# ECU_1A.net
KiCad netlist of a schematic drawn in EAGLE
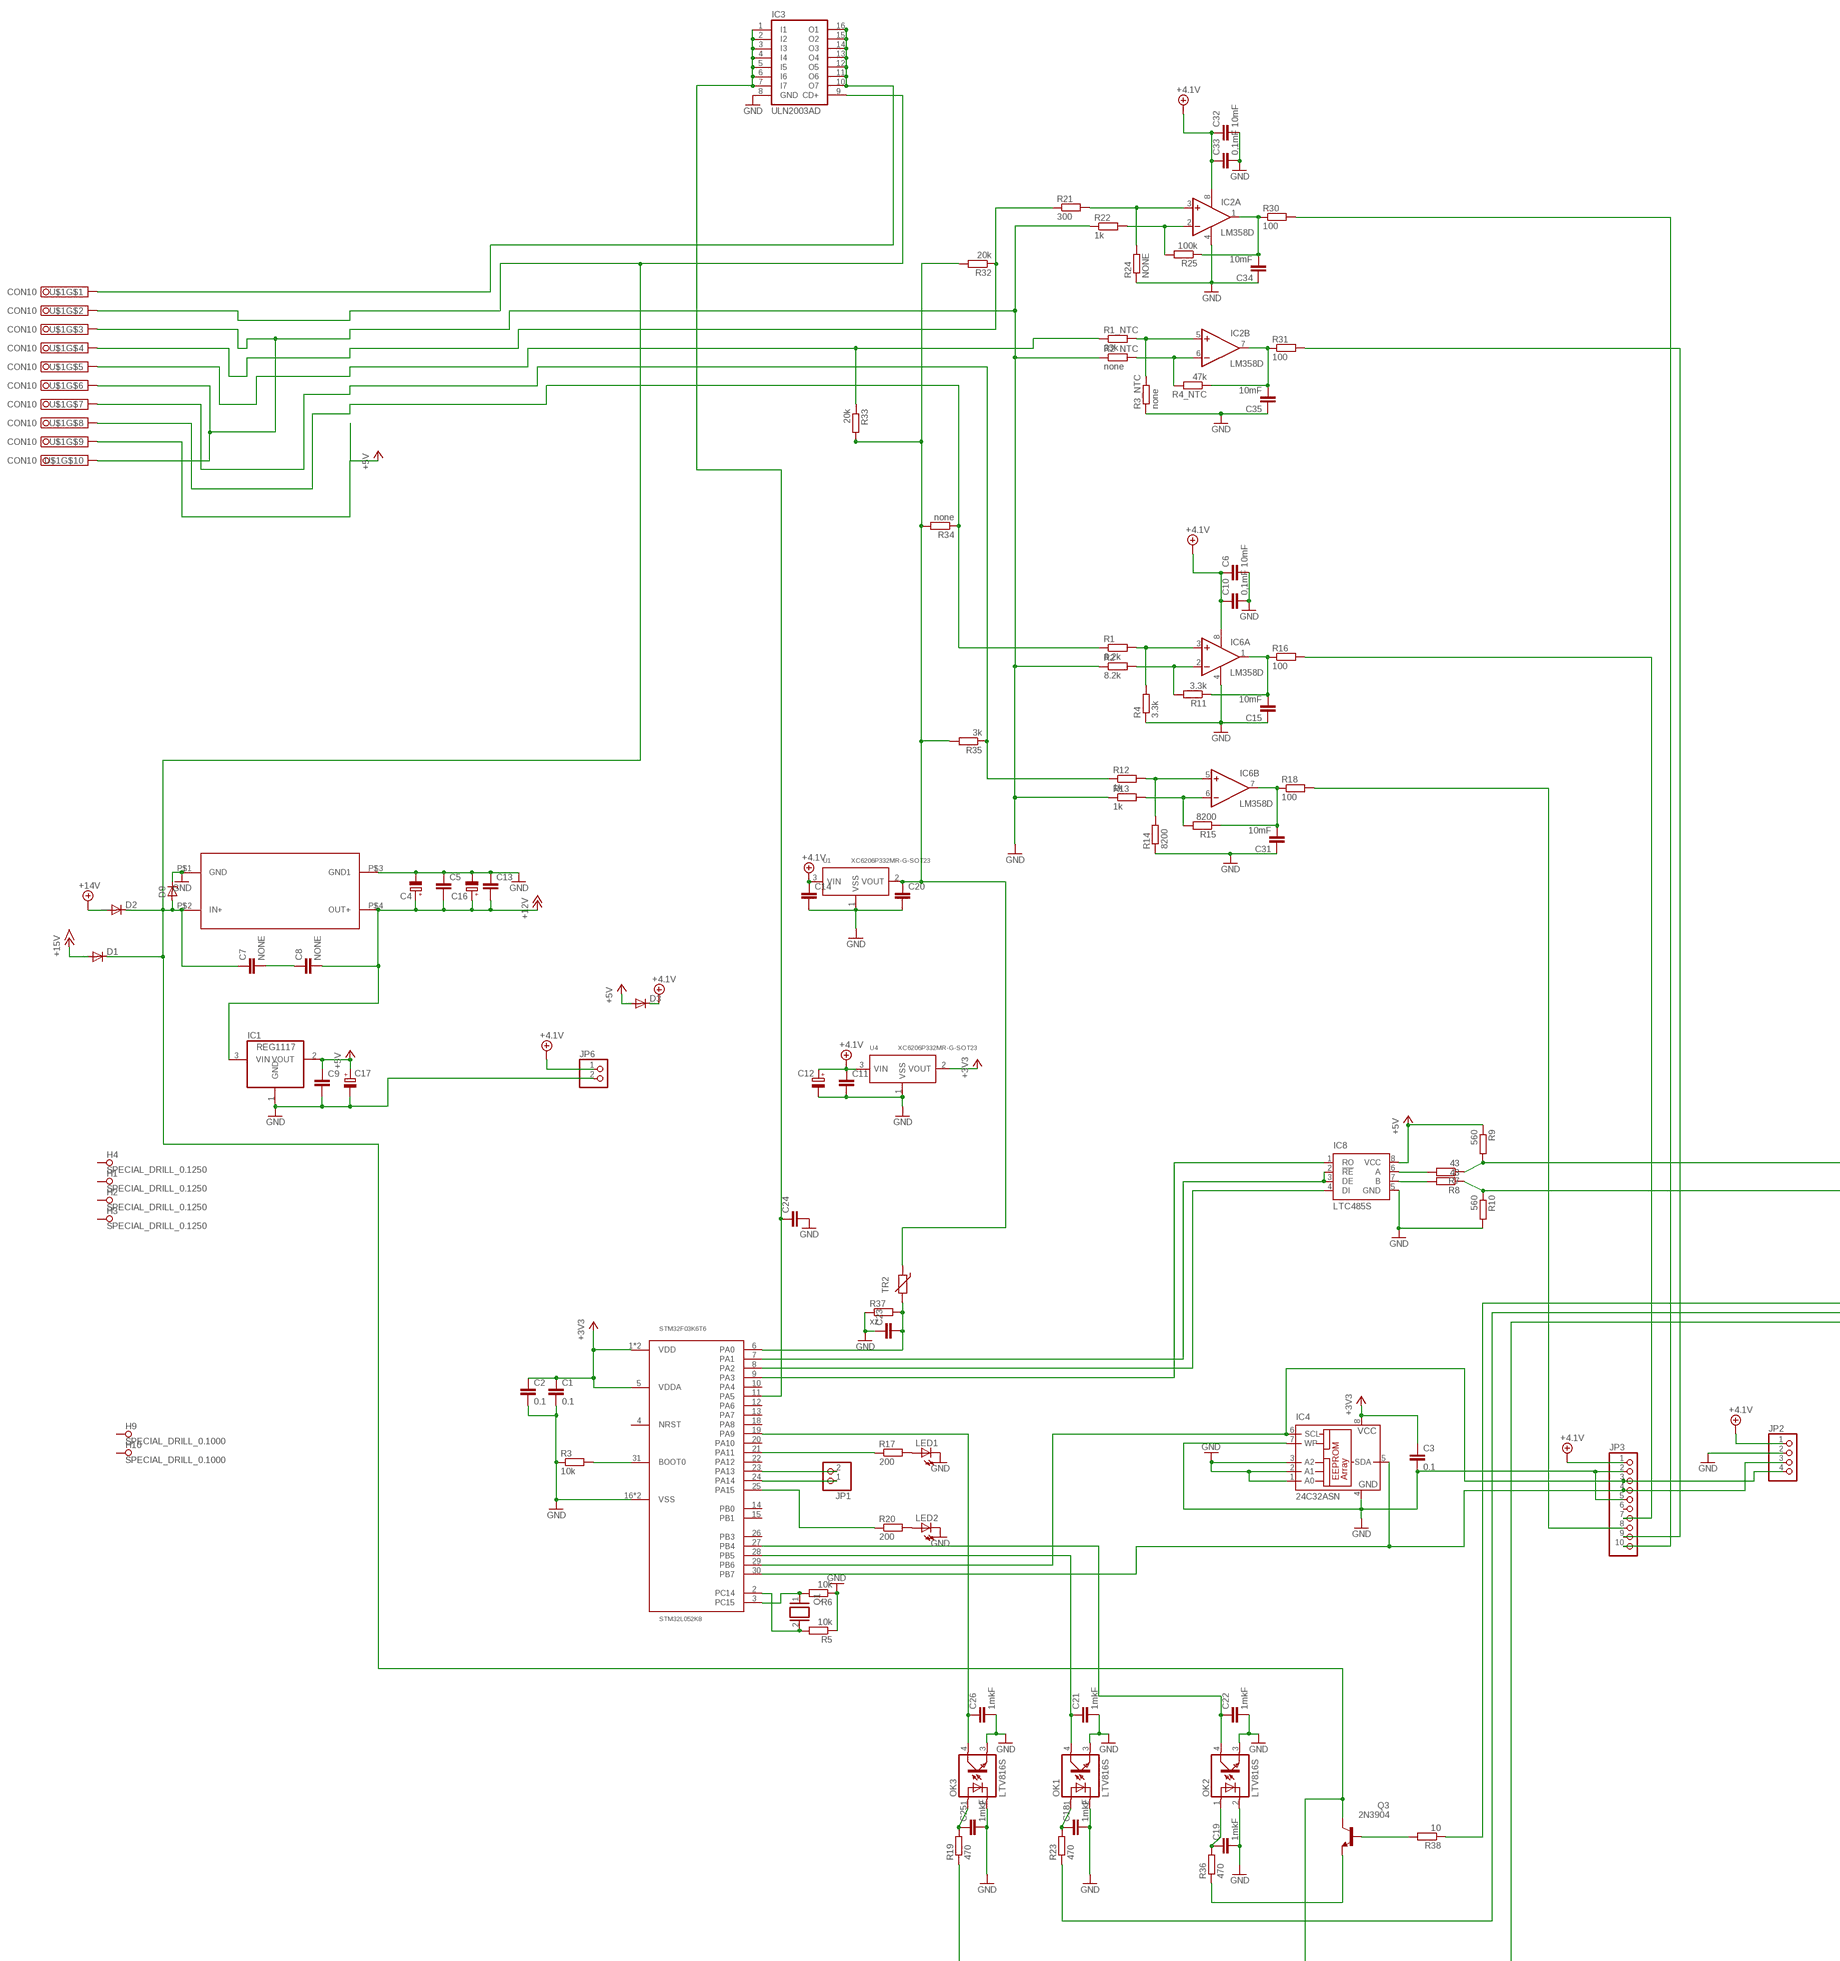
[diagram p0: schematic, sheet 1, part 1 of 3]
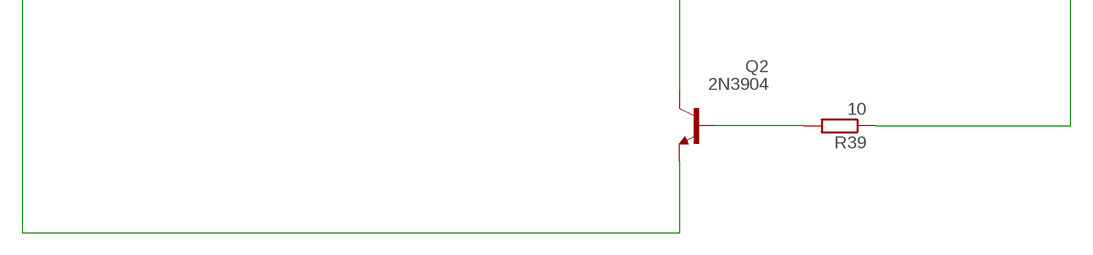
[diagram p1: schematic, sheet 1, part 2 of 3]
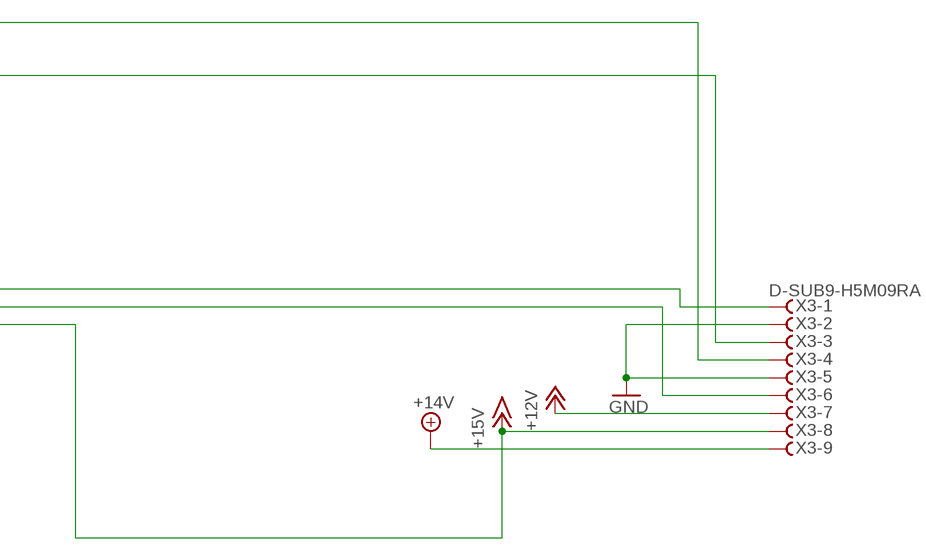
[diagram p2: schematic, sheet 1, part 3 of 3]

(export (version "E")
  (design (tool "Eeschema 10.0.6"))
  (components
    (comp (ref "C1")
      (value "0.1")
      (footprint "eagle-import:C0805")
      (libsource (lib "eagle-import") (part "rcl_C-EUC0805"))
    )
    (comp (ref "C2")
      (value "0.1")
      (footprint "eagle-import:C0805")
      (libsource (lib "eagle-import") (part "rcl_C-EUC0805"))
    )
    (comp (ref "C3")
      (value "0.1")
      (footprint "eagle-import:C0805")
      (libsource (lib "eagle-import") (part "rcl_C-EUC0805"))
    )
    (comp (ref "C4")
      (value "CPOL-EUE2.5-6")
      (footprint "eagle-import:E2,5-6")
      (libsource (lib "eagle-import") (part "CPOL-EUE2.5-6"))
    )
    (comp (ref "C5")
      (value "C-EUC0805")
      (footprint "eagle-import:C0805")
      (libsource (lib "eagle-import") (part "C-EUC0805"))
    )
    (comp (ref "C6")
      (value "10mF")
      (footprint "eagle-import:C0805")
      (libsource (lib "eagle-import") (part "C-EUC0805"))
    )
    (comp (ref "C7")
      (value "NONE")
      (footprint "eagle-import:C0805")
      (libsource (lib "eagle-import") (part "C-EUC0805"))
    )
    (comp (ref "C8")
      (value "NONE")
      (footprint "eagle-import:C0805")
      (libsource (lib "eagle-import") (part "C-EUC0805"))
    )
    (comp (ref "C9")
      (value "C-EUC0805")
      (footprint "eagle-import:C0805")
      (libsource (lib "eagle-import") (part "C-EUC0805"))
    )
    (comp (ref "C10")
      (value "0,1mF")
      (footprint "eagle-import:C0805")
      (libsource (lib "eagle-import") (part "C-EUC0805"))
    )
    (comp (ref "C11")
      (value "C-EUC0805")
      (footprint "eagle-import:C0805")
      (libsource (lib "eagle-import") (part "C-EUC0805"))
    )
    (comp (ref "C12")
      (value "CPOL-EUE2.5-6")
      (footprint "eagle-import:E2,5-6")
      (libsource (lib "eagle-import") (part "CPOL-EUE2.5-6"))
    )
    (comp (ref "C13")
      (value "C-EUC0805")
      (footprint "eagle-import:C0805")
      (libsource (lib "eagle-import") (part "C-EUC0805"))
    )
    (comp (ref "C14")
      (value "C-EUC0805")
      (footprint "eagle-import:C0805")
      (libsource (lib "eagle-import") (part "C-EUC0805"))
    )
    (comp (ref "C15")
      (value "10mF")
      (footprint "eagle-import:C0805")
      (libsource (lib "eagle-import") (part "C-EUC0805"))
    )
    (comp (ref "C16")
      (value "CPOL-EUE5-10.5")
      (footprint "eagle-import:E5-10,5")
      (libsource (lib "eagle-import") (part "rcl_CPOL-EUE5-10.5"))
    )
    (comp (ref "C17")
      (value "CPOL-EUE2,5-6E")
      (footprint "eagle-import:E2,5-6E")
      (libsource (lib "eagle-import") (part "rcl_CPOL-EUE2,5-6E"))
    )
    (comp (ref "C18")
      (value "1mkF")
      (footprint "eagle-import:C0805")
      (libsource (lib "eagle-import") (part "rcl_C-EUC0805"))
    )
    (comp (ref "C19")
      (value "1mkF")
      (footprint "eagle-import:C0805")
      (libsource (lib "eagle-import") (part "rcl_C-EUC0805"))
    )
    (comp (ref "C20")
      (value "C-EUC0805")
      (footprint "eagle-import:C0805")
      (libsource (lib "eagle-import") (part "C-EUC0805"))
    )
    (comp (ref "C21")
      (value "1mkF")
      (footprint "eagle-import:C0805")
      (libsource (lib "eagle-import") (part "rcl_C-EUC0805"))
    )
    (comp (ref "C22")
      (value "1mkF")
      (footprint "eagle-import:C0805")
      (libsource (lib "eagle-import") (part "rcl_C-EUC0805"))
    )
    (comp (ref "C23")
      (value "C-EUC0805")
      (footprint "eagle-import:C0805")
      (libsource (lib "eagle-import") (part "C-EUC0805"))
    )
    (comp (ref "C24")
      (value "C-EUC0805")
      (footprint "eagle-import:C0805")
      (libsource (lib "eagle-import") (part "C-EUC0805"))
    )
    (comp (ref "C25")
      (value "1mkF")
      (footprint "eagle-import:C0805")
      (libsource (lib "eagle-import") (part "rcl_C-EUC0805"))
    )
    (comp (ref "C26")
      (value "1mkF")
      (footprint "eagle-import:C0805")
      (libsource (lib "eagle-import") (part "rcl_C-EUC0805"))
    )
    (comp (ref "C31")
      (value "10mF")
      (footprint "eagle-import:C0805")
      (libsource (lib "eagle-import") (part "C-EUC0805"))
    )
    (comp (ref "C32")
      (value "10mF")
      (footprint "eagle-import:C0805")
      (libsource (lib "eagle-import") (part "C-EUC0805"))
    )
    (comp (ref "C33")
      (value "0,1mF")
      (footprint "eagle-import:C0805")
      (libsource (lib "eagle-import") (part "C-EUC0805"))
    )
    (comp (ref "C34")
      (value "10mF")
      (footprint "eagle-import:C0805")
      (libsource (lib "eagle-import") (part "C-EUC0805"))
    )
    (comp (ref "C35")
      (value "10mF")
      (footprint "eagle-import:C0805")
      (libsource (lib "eagle-import") (part "C-EUC0805"))
    )
    (comp (ref "D1")
      (value "DIODE-DO-214AC")
      (footprint "eagle-import:DO-214AC")
      (libsource (lib "eagle-import") (part "DIODE-DO-214AC"))
    )
    (comp (ref "D2")
      (value "DIODE-DO-214AC")
      (footprint "eagle-import:DO-214AC")
      (libsource (lib "eagle-import") (part "DIODE-DO-214AC"))
    )
    (comp (ref "D3")
      (value "DIODE-DO-214AC")
      (footprint "eagle-import:DO-214AC")
      (libsource (lib "eagle-import") (part "DIODE-DO-214AC"))
    )
    (comp (ref "D9")
      (value "ZENER-DIODEZD-7.5")
      (footprint "eagle-import:ZDIO-7.5")
      (libsource (lib "eagle-import") (part "ZENER-DIODEZD-7.5"))
    )
    (comp (ref "H1")
      (value "SPECIAL_DRILL_0.1250")
      (footprint "eagle-import:PAD_0.1250")
      (libsource (lib "eagle-import") (part "SPECIAL_DRILL_0.1250"))
    )
    (comp (ref "H2")
      (value "SPECIAL_DRILL_0.1250")
      (footprint "eagle-import:PAD_0.1250")
      (libsource (lib "eagle-import") (part "SPECIAL_DRILL_0.1250"))
    )
    (comp (ref "H3")
      (value "SPECIAL_DRILL_0.1250")
      (footprint "eagle-import:PAD_0.1250")
      (libsource (lib "eagle-import") (part "SPECIAL_DRILL_0.1250"))
    )
    (comp (ref "H4")
      (value "SPECIAL_DRILL_0.1250")
      (footprint "eagle-import:PAD_0.1250")
      (libsource (lib "eagle-import") (part "SPECIAL_DRILL_0.1250"))
    )
    (comp (ref "H9")
      (value "SPECIAL_DRILL_0.1000")
      (footprint "eagle-import:PAD_0.1000")
      (libsource (lib "eagle-import") (part "SPECIAL_DRILL_0.1000"))
    )
    (comp (ref "H10")
      (value "SPECIAL_DRILL_0.1000")
      (footprint "eagle-import:PAD_0.1000")
      (libsource (lib "eagle-import") (part "SPECIAL_DRILL_0.1000"))
    )
    (comp (ref "IC1")
      (value "REG1117")
      (footprint "eagle-import:SOT223")
      (libsource (lib "eagle-import") (part "REG1117"))
    )
    (comp (ref "IC2")
      (value "LM358D")
      (footprint "eagle-import:SO08")
      (libsource (lib "eagle-import") (part "LM358D"))
    )
    (comp (ref "IC3")
      (value "ULN2003AD")
      (footprint "eagle-import:SO16")
      (libsource (lib "eagle-import") (part "ULN2003AD"))
    )
    (comp (ref "IC4")
      (value "24C32ASN")
      (footprint "eagle-import:SO-08")
      (fields (field (name "MPN") "IS24C32A-2GLI"))
      (libsource (lib "eagle-import") (part "24SNC32A"))
    )
    (comp (ref "IC6")
      (value "LM358D")
      (footprint "eagle-import:SO08")
      (libsource (lib "eagle-import") (part "LM358D"))
    )
    (comp (ref "IC8")
      (value "LTC485S")
      (footprint "eagle-import:SOIC8")
      (libsource (lib "eagle-import") (part "LTC485S"))
    )
    (comp (ref "JP1")
      (value "PINHD-1X2")
      (footprint "eagle-import:1X02")
      (libsource (lib "eagle-import") (part "PINHD-1X2"))
    )
    (comp (ref "JP2")
      (value "PINHD-1X4")
      (footprint "eagle-import:1X04")
      (libsource (lib "eagle-import") (part "PINHD-1X4"))
    )
    (comp (ref "JP3")
      (value "PINHD-1X10")
      (footprint "eagle-import:1X10")
      (libsource (lib "eagle-import") (part "PINHD-1X10"))
    )
    (comp (ref "JP6")
      (value "PINHD-1X2")
      (footprint "eagle-import:1X02")
      (libsource (lib "eagle-import") (part "PINHD-1X2"))
    )
    (comp (ref "LED1")
      (value "LEDCHIPLED_1206")
      (footprint "eagle-import:CHIPLED_1206")
      (libsource (lib "eagle-import") (part "LEDCHIPLED_1206"))
    )
    (comp (ref "LED2")
      (value "LEDCHIPLED_1206")
      (footprint "eagle-import:CHIPLED_1206")
      (libsource (lib "eagle-import") (part "LEDCHIPLED_1206"))
    )
    (comp (ref "OK1")
      (value "LTV816S")
      (footprint "eagle-import:SMD4")
      (libsource (lib "eagle-import") (part "LTV816S"))
    )
    (comp (ref "OK2")
      (value "LTV816S")
      (footprint "eagle-import:SMD4")
      (libsource (lib "eagle-import") (part "LTV816S"))
    )
    (comp (ref "OK3")
      (value "LTV816S")
      (footprint "eagle-import:SMD4")
      (libsource (lib "eagle-import") (part "LTV816S"))
    )
    (comp (ref "Q1")
      (value "XTAL/S")
      (footprint "eagle-import:QS")
      (libsource (lib "eagle-import") (part "XTAL/S"))
    )
    (comp (ref "Q2")
      (value "2N3904")
      (footprint "eagle-import:TO92")
      (libsource (lib "eagle-import") (part "2N3904"))
    )
    (comp (ref "Q3")
      (value "2N3904")
      (footprint "eagle-import:TO92")
      (libsource (lib "eagle-import") (part "2N3904"))
    )
    (comp (ref "R1")
      (value "8.2k")
      (footprint "eagle-import:R0805")
      (libsource (lib "eagle-import") (part "R-EU_R0805"))
    )
    (comp (ref "R1_NTC")
      (value "33k")
      (footprint "eagle-import:R0805")
      (libsource (lib "eagle-import") (part "R-EU_R0805"))
    )
    (comp (ref "R2")
      (value "8.2k")
      (footprint "eagle-import:R0805")
      (libsource (lib "eagle-import") (part "R-EU_R0805"))
    )
    (comp (ref "R2_NTC")
      (value "none")
      (footprint "eagle-import:R0805")
      (libsource (lib "eagle-import") (part "R-EU_R0805"))
    )
    (comp (ref "R3")
      (value "10k")
      (footprint "eagle-import:R0805")
      (libsource (lib "eagle-import") (part "R-EU_R0805"))
    )
    (comp (ref "R3_NTC")
      (value "none")
      (footprint "eagle-import:R0805")
      (libsource (lib "eagle-import") (part "R-EU_R0805"))
    )
    (comp (ref "R4")
      (value "3.3k")
      (footprint "eagle-import:R0805")
      (libsource (lib "eagle-import") (part "R-EU_R0805"))
    )
    (comp (ref "R4_NTC")
      (value "47k")
      (footprint "eagle-import:R0805")
      (libsource (lib "eagle-import") (part "R-EU_R0805"))
    )
    (comp (ref "R5")
      (value "10k")
      (footprint "eagle-import:R0805")
      (libsource (lib "eagle-import") (part "R-EU_R0805"))
    )
    (comp (ref "R6")
      (value "10k")
      (footprint "eagle-import:R0805")
      (libsource (lib "eagle-import") (part "R-EU_R0805"))
    )
    (comp (ref "R7")
      (value "43")
      (footprint "eagle-import:R0805")
      (libsource (lib "eagle-import") (part "R-EU_R0805"))
    )
    (comp (ref "R8")
      (value "43")
      (footprint "eagle-import:R0805")
      (libsource (lib "eagle-import") (part "R-EU_R0805"))
    )
    (comp (ref "R9")
      (value "560")
      (footprint "eagle-import:R0805")
      (libsource (lib "eagle-import") (part "R-EU_R0805"))
    )
    (comp (ref "R10")
      (value "560")
      (footprint "eagle-import:R0805")
      (libsource (lib "eagle-import") (part "R-EU_R0805"))
    )
    (comp (ref "R11")
      (value "3.3k")
      (footprint "eagle-import:R0805")
      (libsource (lib "eagle-import") (part "R-EU_R0805"))
    )
    (comp (ref "R12")
      (value "1k")
      (footprint "eagle-import:R0805")
      (libsource (lib "eagle-import") (part "R-EU_R0805"))
    )
    (comp (ref "R13")
      (value "1k")
      (footprint "eagle-import:R0805")
      (libsource (lib "eagle-import") (part "R-EU_R0805"))
    )
    (comp (ref "R14")
      (value "8200")
      (footprint "eagle-import:R0805")
      (libsource (lib "eagle-import") (part "R-EU_R0805"))
    )
    (comp (ref "R15")
      (value "8200")
      (footprint "eagle-import:R0805")
      (libsource (lib "eagle-import") (part "R-EU_R0805"))
    )
    (comp (ref "R16")
      (value "100")
      (footprint "eagle-import:R0805")
      (libsource (lib "eagle-import") (part "R-EU_R0805"))
    )
    (comp (ref "R17")
      (value "200")
      (footprint "eagle-import:R0805")
      (libsource (lib "eagle-import") (part "R-EU_R0805"))
    )
    (comp (ref "R18")
      (value "100")
      (footprint "eagle-import:R0805")
      (libsource (lib "eagle-import") (part "R-EU_R0805"))
    )
    (comp (ref "R19")
      (value "470")
      (footprint "eagle-import:R0805")
      (libsource (lib "eagle-import") (part "R-EU_R0805"))
    )
    (comp (ref "R20")
      (value "200")
      (footprint "eagle-import:R0805")
      (libsource (lib "eagle-import") (part "R-EU_R0805"))
    )
    (comp (ref "R21")
      (value "300")
      (footprint "eagle-import:R0805")
      (libsource (lib "eagle-import") (part "R-EU_R0805"))
    )
    (comp (ref "R22")
      (value "1k")
      (footprint "eagle-import:R0805")
      (libsource (lib "eagle-import") (part "R-EU_R0805"))
    )
    (comp (ref "R23")
      (value "470")
      (footprint "eagle-import:R0805")
      (libsource (lib "eagle-import") (part "R-EU_R0805"))
    )
    (comp (ref "R24")
      (value "NONE")
      (footprint "eagle-import:R0805")
      (libsource (lib "eagle-import") (part "R-EU_R0805"))
    )
    (comp (ref "R25")
      (value "100k")
      (footprint "eagle-import:R0805")
      (libsource (lib "eagle-import") (part "R-EU_R0805"))
    )
    (comp (ref "R30")
      (value "100")
      (footprint "eagle-import:R0805")
      (libsource (lib "eagle-import") (part "R-EU_R0805"))
    )
    (comp (ref "R31")
      (value "100")
      (footprint "eagle-import:R0805")
      (libsource (lib "eagle-import") (part "R-EU_R0805"))
    )
    (comp (ref "R32")
      (value "20k")
      (footprint "eagle-import:R0805")
      (libsource (lib "eagle-import") (part "R-EU_R0805"))
    )
    (comp (ref "R33")
      (value "20k")
      (footprint "eagle-import:R0805")
      (libsource (lib "eagle-import") (part "R-EU_R0805"))
    )
    (comp (ref "R34")
      (value "none")
      (footprint "eagle-import:R0805")
      (libsource (lib "eagle-import") (part "R-EU_R0805"))
    )
    (comp (ref "R35")
      (value "3k")
      (footprint "eagle-import:R0805")
      (libsource (lib "eagle-import") (part "R-EU_R0805"))
    )
    (comp (ref "R36")
      (value "470")
      (footprint "eagle-import:R0805")
      (libsource (lib "eagle-import") (part "R-EU_R0805"))
    )
    (comp (ref "R37")
      (value "xz")
      (footprint "eagle-import:R0805")
      (libsource (lib "eagle-import") (part "R-EU_R0805"))
    )
    (comp (ref "R38")
      (value "10")
      (footprint "eagle-import:R0805")
      (libsource (lib "eagle-import") (part "R-EU_R0805"))
    )
    (comp (ref "R39")
      (value "10")
      (footprint "eagle-import:R0805")
      (libsource (lib "eagle-import") (part "R-EU_R0805"))
    )
    (comp (ref "STM32F03K6T6")
      (value "STM32L052K8")
      (footprint "eagle-import:LQFP32-7X7")
      (libsource (lib "eagle-import") (part "STM32L052K8"))
    )
    (comp (ref "TR2")
      (value "THERMISTOR_R-2,5")
      (footprint "eagle-import:RS-2,5")
      (libsource (lib "eagle-import") (part "THERMISTOR_R-2,5"))
    )
    (comp (ref "U$1")
      (value "CON10")
      (footprint "eagle-import:CON10")
      (libsource (lib "eagle-import") (part "CON10"))
    )
    (comp (ref "U$2")
      (value "DC24_DC5")
      (footprint "eagle-import:SLIM_MOUNT")
      (libsource (lib "eagle-import") (part "DC24_DC5"))
    )
    (comp (ref "U1")
      (value "XC6206P332MR-G-SOT23")
      (footprint "eagle-import:SOT-23")
      (fields (field (name "MPN") "XC6206P332MR-G"))
      (libsource (lib "eagle-import") (part "PMIC-LDO-XC6206P332MR-G(SOT23)"))
    )
    (comp (ref "U4")
      (value "XC6206P332MR-G-SOT23")
      (footprint "eagle-import:SOT-23")
      (fields (field (name "MPN") "XC6206P332MR-G"))
      (libsource (lib "eagle-import") (part "PMIC-LDO-XC6206P332MR-G(SOT23)"))
    )
    (comp (ref "X3")
      (value "D-SUB9-H5M09RA")
      (footprint "eagle-import:H5M09RA")
      (libsource (lib "eagle-import") (part "D-SUB9-H5M09RA"))
    )
  )
  (nets
    (net (code "1") (name "+3V3") (class "Default")
      (node (ref "C1") (pin "1") (pinfunction "1_1") (pintype "passive"))
      (node (ref "C2") (pin "1") (pinfunction "1_1") (pintype "passive"))
      (node (ref "C3") (pin "1") (pinfunction "1_1") (pintype "passive"))
      (node (ref "IC4") (pin "8") (pinfunction "VCC_8") (pintype "power_in"))
      (node (ref "STM32F03K6T6") (pin "1") (pinfunction "VDD_1") (pintype "bidirectional"))
      (node (ref "STM32F03K6T6") (pin "17") (pinfunction "VDD_17") (pintype "bidirectional"))
      (node (ref "STM32F03K6T6") (pin "5") (pinfunction "VDDA_5") (pintype "bidirectional"))
      (node (ref "U4") (pin "2") (pinfunction "VOUT_2") (pintype "output"))
    )
    (net (code "2") (name "+4.1V") (class "Default")
      (node (ref "C10") (pin "1") (pinfunction "1_1") (pintype "passive"))
      (node (ref "C11") (pin "1") (pinfunction "1_1") (pintype "passive"))
      (node (ref "C12") (pin "+") (pinfunction "+_+") (pintype "passive"))
      (node (ref "C14") (pin "1") (pinfunction "1_1") (pintype "passive"))
      (node (ref "C32") (pin "1") (pinfunction "1_1") (pintype "passive"))
      (node (ref "C33") (pin "1") (pinfunction "1_1") (pintype "passive"))
      (node (ref "C6") (pin "1") (pinfunction "1_1") (pintype "passive"))
      (node (ref "D3") (pin "C") (pinfunction "C_C") (pintype "passive"))
      (node (ref "IC2") (pin "8") (pinfunction "V+_8") (pintype "power_in"))
      (node (ref "IC6") (pin "8") (pinfunction "V+_8") (pintype "power_in"))
      (node (ref "JP2") (pin "1") (pinfunction "1_1") (pintype "passive"))
      (node (ref "JP3") (pin "1") (pinfunction "1_1") (pintype "passive"))
      (node (ref "JP6") (pin "1") (pinfunction "1_1") (pintype "passive"))
      (node (ref "U1") (pin "3") (pinfunction "VIN_3") (pintype "input"))
      (node (ref "U4") (pin "3") (pinfunction "VIN_3") (pintype "input"))
    )
    (net (code "3") (name "+5V") (class "Default")
      (node (ref "C17") (pin "+") (pinfunction "+_+") (pintype "passive"))
      (node (ref "C9") (pin "1") (pinfunction "1_1") (pintype "passive"))
      (node (ref "D3") (pin "A") (pinfunction "A_A") (pintype "passive"))
      (node (ref "IC1") (pin "2") (pinfunction "VOUT_2") (pintype "output"))
      (node (ref "IC8") (pin "8") (pinfunction "VCC_8") (pintype "input"))
      (node (ref "R9") (pin "1") (pinfunction "1_1") (pintype "passive"))
      (node (ref "U$1") (pin "9") (pinfunction "K_9") (pintype "passive"))
    )
    (net (code "4") (name "+12V") (class "Default")
      (node (ref "C13") (pin "2") (pinfunction "2_2") (pintype "passive"))
      (node (ref "C16") (pin "+") (pinfunction "+_+") (pintype "passive"))
      (node (ref "C4") (pin "+") (pinfunction "+_+") (pintype "passive"))
      (node (ref "C5") (pin "2") (pinfunction "2_2") (pintype "passive"))
      (node (ref "C8") (pin "2") (pinfunction "2_2") (pintype "passive"))
      (node (ref "IC1") (pin "3") (pinfunction "VIN_3") (pintype "input"))
      (node (ref "U$2") (pin "P$4") (pinfunction "OUT+_P$4") (pintype "bidirectional"))
      (node (ref "X3") (pin "7") (pinfunction "F_7") (pintype "passive"))
    )
    (net (code "5") (name "+14V") (class "Default")
      (node (ref "D2") (pin "A") (pinfunction "A_A") (pintype "passive"))
      (node (ref "X3") (pin "9") (pinfunction "F_9") (pintype "passive"))
    )
    (net (code "6") (name "+15V") (class "Default")
      (node (ref "D1") (pin "A") (pinfunction "A_A") (pintype "passive"))
      (node (ref "R39") (pin "1") (pinfunction "1_1") (pintype "passive"))
      (node (ref "X3") (pin "8") (pinfunction "F_8") (pintype "passive"))
    )
    (net (code "7") (name "GND") (class "Default")
      (node (ref "C1") (pin "2") (pinfunction "2_2") (pintype "passive"))
      (node (ref "C10") (pin "2") (pinfunction "2_2") (pintype "passive"))
      (node (ref "C11") (pin "2") (pinfunction "2_2") (pintype "passive"))
      (node (ref "C12") (pin "-") (pinfunction "-_-") (pintype "passive"))
      (node (ref "C13") (pin "1") (pinfunction "1_1") (pintype "passive"))
      (node (ref "C14") (pin "2") (pinfunction "2_2") (pintype "passive"))
      (node (ref "C15") (pin "1") (pinfunction "1_1") (pintype "passive"))
      (node (ref "C16") (pin "-") (pinfunction "-_-") (pintype "passive"))
      (node (ref "C17") (pin "-") (pinfunction "-_-") (pintype "passive"))
      (node (ref "C18") (pin "2") (pinfunction "2_2") (pintype "passive"))
      (node (ref "C19") (pin "2") (pinfunction "2_2") (pintype "passive"))
      (node (ref "C2") (pin "2") (pinfunction "2_2") (pintype "passive"))
      (node (ref "C20") (pin "2") (pinfunction "2_2") (pintype "passive"))
      (node (ref "C21") (pin "2") (pinfunction "2_2") (pintype "passive"))
      (node (ref "C22") (pin "2") (pinfunction "2_2") (pintype "passive"))
      (node (ref "C23") (pin "1") (pinfunction "1_1") (pintype "passive"))
      (node (ref "C24") (pin "2") (pinfunction "2_2") (pintype "passive"))
      (node (ref "C25") (pin "2") (pinfunction "2_2") (pintype "passive"))
      (node (ref "C26") (pin "2") (pinfunction "2_2") (pintype "passive"))
      (node (ref "C3") (pin "2") (pinfunction "2_2") (pintype "passive"))
      (node (ref "C31") (pin "1") (pinfunction "1_1") (pintype "passive"))
      (node (ref "C32") (pin "2") (pinfunction "2_2") (pintype "passive"))
      (node (ref "C33") (pin "2") (pinfunction "2_2") (pintype "passive"))
      (node (ref "C34") (pin "1") (pinfunction "1_1") (pintype "passive"))
      (node (ref "C35") (pin "1") (pinfunction "1_1") (pintype "passive"))
      (node (ref "C4") (pin "-") (pinfunction "-_-") (pintype "passive"))
      (node (ref "C5") (pin "1") (pinfunction "1_1") (pintype "passive"))
      (node (ref "C6") (pin "2") (pinfunction "2_2") (pintype "passive"))
      (node (ref "C9") (pin "2") (pinfunction "2_2") (pintype "passive"))
      (node (ref "D9") (pin "C") (pinfunction "C_C") (pintype "passive"))
      (node (ref "IC1") (pin "1") (pinfunction "GND_1") (pintype "power_in"))
      (node (ref "IC2") (pin "4") (pinfunction "V-_4") (pintype "power_in"))
      (node (ref "IC3") (pin "8") (pinfunction "GND_8") (pintype "power_in"))
      (node (ref "IC4") (pin "1") (pinfunction "A0_1") (pintype "input"))
      (node (ref "IC4") (pin "2") (pinfunction "A1_2") (pintype "input"))
      (node (ref "IC4") (pin "3") (pinfunction "A2_3") (pintype "input"))
      (node (ref "IC4") (pin "4") (pinfunction "GND_4") (pintype "power_in"))
      (node (ref "IC4") (pin "7") (pinfunction "WP_7") (pintype "input"))
      (node (ref "IC6") (pin "4") (pinfunction "V-_4") (pintype "power_in"))
      (node (ref "IC8") (pin "5") (pinfunction "GND_5") (pintype "input"))
      (node (ref "JP2") (pin "2") (pinfunction "2_2") (pintype "passive"))
      (node (ref "JP3") (pin "2") (pinfunction "2_2") (pintype "passive"))
      (node (ref "JP3") (pin "5") (pinfunction "5_5") (pintype "passive"))
      (node (ref "JP6") (pin "2") (pinfunction "2_2") (pintype "passive"))
      (node (ref "LED1") (pin "C") (pinfunction "C_C") (pintype "passive"))
      (node (ref "LED2") (pin "C") (pinfunction "C_C") (pintype "passive"))
      (node (ref "OK1") (pin "2") (pinfunction "C_2") (pintype "passive"))
      (node (ref "OK1") (pin "3") (pinfunction "EMIT_3") (pintype "passive"))
      (node (ref "OK2") (pin "2") (pinfunction "C_2") (pintype "passive"))
      (node (ref "OK2") (pin "3") (pinfunction "EMIT_3") (pintype "passive"))
      (node (ref "OK3") (pin "2") (pinfunction "C_2") (pintype "passive"))
      (node (ref "OK3") (pin "3") (pinfunction "EMIT_3") (pintype "passive"))
      (node (ref "R10") (pin "2") (pinfunction "2_2") (pintype "passive"))
      (node (ref "R13") (pin "1") (pinfunction "1_1") (pintype "passive"))
      (node (ref "R14") (pin "1") (pinfunction "1_1") (pintype "passive"))
      (node (ref "R2") (pin "1") (pinfunction "1_1") (pintype "passive"))
      (node (ref "R22") (pin "1") (pinfunction "1_1") (pintype "passive"))
      (node (ref "R24") (pin "1") (pinfunction "1_1") (pintype "passive"))
      (node (ref "R2_NTC") (pin "1") (pinfunction "1_1") (pintype "passive"))
      (node (ref "R3") (pin "1") (pinfunction "1_1") (pintype "passive"))
      (node (ref "R37") (pin "1") (pinfunction "1_1") (pintype "passive"))
      (node (ref "R3_NTC") (pin "1") (pinfunction "1_1") (pintype "passive"))
      (node (ref "R4") (pin "1") (pinfunction "1_1") (pintype "passive"))
      (node (ref "R5") (pin "1") (pinfunction "1_1") (pintype "passive"))
      (node (ref "R6") (pin "1") (pinfunction "1_1") (pintype "passive"))
      (node (ref "STM32F03K6T6") (pin "16") (pinfunction "VSS_16") (pintype "bidirectional"))
      (node (ref "STM32F03K6T6") (pin "32") (pinfunction "VSS_32") (pintype "bidirectional"))
      (node (ref "U$1") (pin "10") (pinfunction "K_10") (pintype "passive"))
      (node (ref "U$1") (pin "3") (pinfunction "K_3") (pintype "passive"))
      (node (ref "U$1") (pin "6") (pinfunction "K_6") (pintype "passive"))
      (node (ref "U$2") (pin "P$1") (pinfunction "GND_P$1") (pintype "bidirectional"))
      (node (ref "U$2") (pin "P$3") (pinfunction "GND1_P$3") (pintype "bidirectional"))
      (node (ref "U1") (pin "1") (pinfunction "VSS_1") (pintype "power_in"))
      (node (ref "U4") (pin "1") (pinfunction "VSS_1") (pintype "power_in"))
      (node (ref "X3") (pin "2") (pinfunction "F_2") (pintype "passive"))
      (node (ref "X3") (pin "5") (pinfunction "F_5") (pintype "passive"))
    )
    (net (code "8") (name "Net-(C7-Pad2)") (class "Default")
      (node (ref "C7") (pin "2") (pinfunction "2_2") (pintype "passive"))
      (node (ref "C8") (pin "1") (pinfunction "1_1") (pintype "passive"))
    )
    (net (code "9") (name "Net-(IC2A-+IN)") (class "Default")
      (node (ref "IC2") (pin "3") (pinfunction "+IN_3") (pintype "input"))
      (node (ref "R21") (pin "2") (pinfunction "2_2") (pintype "passive"))
      (node (ref "R24") (pin "2") (pinfunction "2_2") (pintype "passive"))
    )
    (net (code "10") (name "Net-(IC2A--IN)") (class "Default")
      (node (ref "IC2") (pin "2") (pinfunction "-IN_2") (pintype "input"))
      (node (ref "R22") (pin "2") (pinfunction "2_2") (pintype "passive"))
      (node (ref "R25") (pin "2") (pinfunction "2_2") (pintype "passive"))
    )
    (net (code "11") (name "Net-(IC2A-OUT)") (class "Default")
      (node (ref "C34") (pin "2") (pinfunction "2_2") (pintype "passive"))
      (node (ref "IC2") (pin "1") (pinfunction "OUT_1") (pintype "output"))
      (node (ref "R25") (pin "1") (pinfunction "1_1") (pintype "passive"))
      (node (ref "R30") (pin "1") (pinfunction "1_1") (pintype "passive"))
    )
    (net (code "12") (name "Net-(IC2B-+IN)") (class "Default")
      (node (ref "IC2") (pin "5") (pinfunction "+IN_5") (pintype "input"))
      (node (ref "R1_NTC") (pin "2") (pinfunction "2_2") (pintype "passive"))
      (node (ref "R3_NTC") (pin "2") (pinfunction "2_2") (pintype "passive"))
    )
    (net (code "13") (name "Net-(IC2B--IN)") (class "Default")
      (node (ref "IC2") (pin "6") (pinfunction "-IN_6") (pintype "input"))
      (node (ref "R2_NTC") (pin "2") (pinfunction "2_2") (pintype "passive"))
      (node (ref "R4_NTC") (pin "2") (pinfunction "2_2") (pintype "passive"))
    )
    (net (code "14") (name "Net-(IC2B-OUT)") (class "Default")
      (node (ref "C35") (pin "2") (pinfunction "2_2") (pintype "passive"))
      (node (ref "IC2") (pin "7") (pinfunction "OUT_7") (pintype "output"))
      (node (ref "R31") (pin "1") (pinfunction "1_1") (pintype "passive"))
      (node (ref "R4_NTC") (pin "1") (pinfunction "1_1") (pintype "passive"))
    )
    (net (code "15") (name "Net-(IC3-CD+)") (class "Default")
      (node (ref "C7") (pin "1") (pinfunction "1_1") (pintype "passive"))
      (node (ref "D1") (pin "C") (pinfunction "C_C") (pintype "passive"))
      (node (ref "D2") (pin "C") (pinfunction "C_C") (pintype "passive"))
      (node (ref "D9") (pin "A") (pinfunction "A_A") (pintype "passive"))
      (node (ref "IC3") (pin "9") (pinfunction "CD+_9") (pintype "passive"))
      (node (ref "Q2") (pin "1") (pinfunction "C_1") (pintype "passive"))
      (node (ref "Q3") (pin "1") (pinfunction "C_1") (pintype "passive"))
      (node (ref "U$1") (pin "2") (pinfunction "K_2") (pintype "passive"))
      (node (ref "U$2") (pin "P$2") (pinfunction "IN+_P$2") (pintype "bidirectional"))
    )
    (net (code "16") (name "Net-(IC3-I1)") (class "Default")
      (node (ref "C24") (pin "1") (pinfunction "1_1") (pintype "passive"))
      (node (ref "IC3") (pin "1") (pinfunction "I1_1") (pintype "input"))
      (node (ref "IC3") (pin "2") (pinfunction "I2_2") (pintype "input"))
      (node (ref "IC3") (pin "3") (pinfunction "I3_3") (pintype "input"))
      (node (ref "IC3") (pin "4") (pinfunction "I4_4") (pintype "input"))
      (node (ref "IC3") (pin "5") (pinfunction "I5_5") (pintype "input"))
      (node (ref "IC3") (pin "6") (pinfunction "I6_6") (pintype "input"))
      (node (ref "IC3") (pin "7") (pinfunction "I7_7") (pintype "input"))
      (node (ref "STM32F03K6T6") (pin "11") (pinfunction "PA5_11") (pintype "bidirectional"))
    )
    (net (code "17") (name "Net-(IC3-O1)") (class "Default")
      (node (ref "IC3") (pin "10") (pinfunction "O7_10") (pintype "open_collector"))
      (node (ref "IC3") (pin "11") (pinfunction "O6_11") (pintype "open_collector"))
      (node (ref "IC3") (pin "12") (pinfunction "O5_12") (pintype "open_collector"))
      (node (ref "IC3") (pin "13") (pinfunction "O4_13") (pintype "open_collector"))
      (node (ref "IC3") (pin "14") (pinfunction "O3_14") (pintype "open_collector"))
      (node (ref "IC3") (pin "15") (pinfunction "O2_15") (pintype "open_collector"))
      (node (ref "IC3") (pin "16") (pinfunction "O1_16") (pintype "open_collector"))
      (node (ref "U$1") (pin "1") (pinfunction "K_1") (pintype "passive"))
    )
    (net (code "18") (name "Net-(IC4-SCL)") (class "Default")
      (node (ref "IC4") (pin "6") (pinfunction "SCL_6") (pintype "input"))
      (node (ref "JP2") (pin "4") (pinfunction "4_4") (pintype "passive"))
      (node (ref "JP3") (pin "3") (pinfunction "3_3") (pintype "passive"))
      (node (ref "STM32F03K6T6") (pin "29") (pinfunction "PB6_29") (pintype "bidirectional"))
    )
    (net (code "19") (name "Net-(IC4-SDA)") (class "Default")
      (node (ref "IC4") (pin "5") (pinfunction "SDA_5") (pintype "bidirectional"))
      (node (ref "JP2") (pin "3") (pinfunction "3_3") (pintype "passive"))
      (node (ref "JP3") (pin "4") (pinfunction "4_4") (pintype "passive"))
      (node (ref "STM32F03K6T6") (pin "30") (pinfunction "PB7_30") (pintype "bidirectional"))
    )
    (net (code "20") (name "Net-(IC6A-+IN)") (class "Default")
      (node (ref "IC6") (pin "3") (pinfunction "+IN_3") (pintype "input"))
      (node (ref "R1") (pin "2") (pinfunction "2_2") (pintype "passive"))
      (node (ref "R4") (pin "2") (pinfunction "2_2") (pintype "passive"))
    )
    (net (code "21") (name "Net-(IC6A--IN)") (class "Default")
      (node (ref "IC6") (pin "2") (pinfunction "-IN_2") (pintype "input"))
      (node (ref "R11") (pin "2") (pinfunction "2_2") (pintype "passive"))
      (node (ref "R2") (pin "2") (pinfunction "2_2") (pintype "passive"))
    )
    (net (code "22") (name "Net-(IC6A-OUT)") (class "Default")
      (node (ref "C15") (pin "2") (pinfunction "2_2") (pintype "passive"))
      (node (ref "IC6") (pin "1") (pinfunction "OUT_1") (pintype "output"))
      (node (ref "R11") (pin "1") (pinfunction "1_1") (pintype "passive"))
      (node (ref "R16") (pin "1") (pinfunction "1_1") (pintype "passive"))
    )
    (net (code "23") (name "Net-(IC6B-+IN)") (class "Default")
      (node (ref "IC6") (pin "5") (pinfunction "+IN_5") (pintype "input"))
      (node (ref "R12") (pin "2") (pinfunction "2_2") (pintype "passive"))
      (node (ref "R14") (pin "2") (pinfunction "2_2") (pintype "passive"))
    )
    (net (code "24") (name "Net-(IC6B--IN)") (class "Default")
      (node (ref "IC6") (pin "6") (pinfunction "-IN_6") (pintype "input"))
      (node (ref "R13") (pin "2") (pinfunction "2_2") (pintype "passive"))
      (node (ref "R15") (pin "2") (pinfunction "2_2") (pintype "passive"))
    )
    (net (code "25") (name "Net-(IC6B-OUT)") (class "Default")
      (node (ref "C31") (pin "2") (pinfunction "2_2") (pintype "passive"))
      (node (ref "IC6") (pin "7") (pinfunction "OUT_7") (pintype "output"))
      (node (ref "R15") (pin "1") (pinfunction "1_1") (pintype "passive"))
      (node (ref "R18") (pin "1") (pinfunction "1_1") (pintype "passive"))
    )
    (net (code "26") (name "Net-(IC8-A)") (class "Default")
      (node (ref "IC8") (pin "6") (pinfunction "A_6") (pintype "bidirectional"))
      (node (ref "R7") (pin "2") (pinfunction "2_2") (pintype "passive"))
    )
    (net (code "27") (name "Net-(IC8-B)") (class "Default")
      (node (ref "IC8") (pin "7") (pinfunction "B_7") (pintype "bidirectional"))
      (node (ref "R8") (pin "2") (pinfunction "2_2") (pintype "passive"))
    )
    (net (code "28") (name "Net-(IC8-DE)") (class "Default")
      (node (ref "IC8") (pin "2") (pinfunction "~{RE}_2") (pintype "input"))
      (node (ref "IC8") (pin "3") (pinfunction "DE_3") (pintype "input"))
      (node (ref "STM32F03K6T6") (pin "7") (pinfunction "PA1_7") (pintype "bidirectional"))
    )
    (net (code "29") (name "Net-(IC8-DI)") (class "Default")
      (node (ref "IC8") (pin "4") (pinfunction "DI_4") (pintype "input"))
      (node (ref "STM32F03K6T6") (pin "8") (pinfunction "PA2_8") (pintype "bidirectional"))
    )
    (net (code "30") (name "Net-(IC8-RO)") (class "Default")
      (node (ref "IC8") (pin "1") (pinfunction "RO_1") (pintype "output"))
      (node (ref "STM32F03K6T6") (pin "9") (pinfunction "PA3_9") (pintype "bidirectional"))
    )
    (net (code "31") (name "Net-(JP3-Pad7)") (class "Default")
      (node (ref "JP3") (pin "7") (pinfunction "7_7") (pintype "passive"))
      (node (ref "R16") (pin "2") (pinfunction "2_2") (pintype "passive"))
    )
    (net (code "32") (name "Net-(JP3-Pad8)") (class "Default")
      (node (ref "JP3") (pin "8") (pinfunction "8_8") (pintype "passive"))
      (node (ref "R18") (pin "2") (pinfunction "2_2") (pintype "passive"))
    )
    (net (code "33") (name "Net-(JP3-Pad9)") (class "Default")
      (node (ref "JP3") (pin "9") (pinfunction "9_9") (pintype "passive"))
      (node (ref "R31") (pin "2") (pinfunction "2_2") (pintype "passive"))
    )
    (net (code "34") (name "Net-(JP3-Pad10)") (class "Default")
      (node (ref "JP3") (pin "10") (pinfunction "10_10") (pintype "passive"))
      (node (ref "R30") (pin "2") (pinfunction "2_2") (pintype "passive"))
    )
    (net (code "35") (name "Net-(LED1-PadA)") (class "Default")
      (node (ref "LED1") (pin "A") (pinfunction "A_A") (pintype "passive"))
      (node (ref "R17") (pin "2") (pinfunction "2_2") (pintype "passive"))
    )
    (net (code "36") (name "Net-(LED2-PadA)") (class "Default")
      (node (ref "LED2") (pin "A") (pinfunction "A_A") (pintype "passive"))
      (node (ref "R20") (pin "2") (pinfunction "2_2") (pintype "passive"))
    )
    (net (code "37") (name "Net-(OK1-A)") (class "Default")
      (node (ref "C18") (pin "1") (pinfunction "1_1") (pintype "passive"))
      (node (ref "OK1") (pin "1") (pinfunction "A_1") (pintype "passive"))
      (node (ref "R23") (pin "2") (pinfunction "2_2") (pintype "passive"))
    )
    (net (code "38") (name "Net-(OK1-COL)") (class "Default")
      (node (ref "C21") (pin "1") (pinfunction "1_1") (pintype "passive"))
      (node (ref "OK1") (pin "4") (pinfunction "COL_4") (pintype "passive"))
      (node (ref "STM32F03K6T6") (pin "28") (pinfunction "PB5_28") (pintype "bidirectional"))
    )
    (net (code "39") (name "Net-(OK2-A)") (class "Default")
      (node (ref "C19") (pin "1") (pinfunction "1_1") (pintype "passive"))
      (node (ref "OK2") (pin "1") (pinfunction "A_1") (pintype "passive"))
      (node (ref "R36") (pin "2") (pinfunction "2_2") (pintype "passive"))
    )
    (net (code "40") (name "Net-(OK2-COL)") (class "Default")
      (node (ref "C22") (pin "1") (pinfunction "1_1") (pintype "passive"))
      (node (ref "OK2") (pin "4") (pinfunction "COL_4") (pintype "passive"))
      (node (ref "STM32F03K6T6") (pin "27") (pinfunction "PB4_27") (pintype "bidirectional"))
    )
    (net (code "41") (name "Net-(OK3-A)") (class "Default")
      (node (ref "C25") (pin "1") (pinfunction "1_1") (pintype "passive"))
      (node (ref "OK3") (pin "1") (pinfunction "A_1") (pintype "passive"))
      (node (ref "R19") (pin "2") (pinfunction "2_2") (pintype "passive"))
    )
    (net (code "42") (name "Net-(OK3-COL)") (class "Default")
      (node (ref "C26") (pin "1") (pinfunction "1_1") (pintype "passive"))
      (node (ref "OK3") (pin "4") (pinfunction "COL_4") (pintype "passive"))
      (node (ref "STM32F03K6T6") (pin "19") (pinfunction "PA9_19") (pintype "bidirectional"))
    )
    (net (code "43") (name "Net-(Q2-B)") (class "Default")
      (node (ref "Q2") (pin "2") (pinfunction "B_2") (pintype "passive"))
      (node (ref "R39") (pin "2") (pinfunction "2_2") (pintype "passive"))
    )
    (net (code "44") (name "Net-(Q2-E)") (class "Default")
      (node (ref "Q2") (pin "3") (pinfunction "E_3") (pintype "passive"))
      (node (ref "R19") (pin "1") (pinfunction "1_1") (pintype "passive"))
    )
    (net (code "45") (name "Net-(Q3-B)") (class "Default")
      (node (ref "Q3") (pin "2") (pinfunction "B_2") (pintype "passive"))
      (node (ref "R38") (pin "2") (pinfunction "2_2") (pintype "passive"))
    )
    (net (code "46") (name "Net-(Q3-E)") (class "Default")
      (node (ref "Q3") (pin "3") (pinfunction "E_3") (pintype "passive"))
      (node (ref "R36") (pin "1") (pinfunction "1_1") (pintype "passive"))
    )
    (net (code "47") (name "Net-(STM32F03K6T6-BOOT0)") (class "Default")
      (node (ref "R3") (pin "2") (pinfunction "2_2") (pintype "passive"))
      (node (ref "STM32F03K6T6") (pin "31") (pinfunction "BOOT0_31") (pintype "bidirectional"))
    )
    (net (code "48") (name "Net-(STM32F03K6T6-PA0)") (class "Default")
      (node (ref "C23") (pin "2") (pinfunction "2_2") (pintype "passive"))
      (node (ref "R37") (pin "2") (pinfunction "2_2") (pintype "passive"))
      (node (ref "STM32F03K6T6") (pin "6") (pinfunction "PA0_6") (pintype "bidirectional"))
      (node (ref "TR2") (pin "2") (pinfunction "2_2") (pintype "passive"))
    )
    (net (code "49") (name "Net-(STM32F03K6T6-PA11)") (class "Default")
      (node (ref "R17") (pin "1") (pinfunction "1_1") (pintype "passive"))
      (node (ref "STM32F03K6T6") (pin "21") (pinfunction "PA11_21") (pintype "bidirectional"))
    )
    (net (code "50") (name "Net-(STM32F03K6T6-PA13)") (class "Default")
      (node (ref "JP1") (pin "2") (pinfunction "2_2") (pintype "passive"))
      (node (ref "STM32F03K6T6") (pin "23") (pinfunction "PA13_23") (pintype "bidirectional"))
    )
    (net (code "51") (name "Net-(STM32F03K6T6-PA14)") (class "Default")
      (node (ref "JP1") (pin "1") (pinfunction "1_1") (pintype "passive"))
      (node (ref "STM32F03K6T6") (pin "24") (pinfunction "PA14_24") (pintype "bidirectional"))
    )
    (net (code "52") (name "Net-(STM32F03K6T6-PA15)") (class "Default")
      (node (ref "R20") (pin "1") (pinfunction "1_1") (pintype "passive"))
      (node (ref "STM32F03K6T6") (pin "25") (pinfunction "PA15_25") (pintype "bidirectional"))
    )
    (net (code "53") (name "Net-(STM32F03K6T6-PC14)") (class "Default")
      (node (ref "Q1") (pin "2") (pinfunction "2_2") (pintype "passive"))
      (node (ref "R5") (pin "2") (pinfunction "2_2") (pintype "passive"))
      (node (ref "STM32F03K6T6") (pin "2") (pinfunction "PC14_2") (pintype "bidirectional"))
    )
    (net (code "54") (name "Net-(STM32F03K6T6-PC15)") (class "Default")
      (node (ref "Q1") (pin "1") (pinfunction "1_1") (pintype "passive"))
      (node (ref "R6") (pin "2") (pinfunction "2_2") (pintype "passive"))
      (node (ref "STM32F03K6T6") (pin "3") (pinfunction "PC15_3") (pintype "bidirectional"))
    )
    (net (code "55") (name "Net-(U$1E-K)") (class "Default")
      (node (ref "R21") (pin "1") (pinfunction "1_1") (pintype "passive"))
      (node (ref "R32") (pin "1") (pinfunction "1_1") (pintype "passive"))
      (node (ref "U$1") (pin "4") (pinfunction "K_4") (pintype "passive"))
    )
    (net (code "56") (name "Net-(U$1F-K)") (class "Default")
      (node (ref "R1_NTC") (pin "1") (pinfunction "1_1") (pintype "passive"))
      (node (ref "R33") (pin "1") (pinfunction "1_1") (pintype "passive"))
      (node (ref "U$1") (pin "5") (pinfunction "K_5") (pintype "passive"))
    )
    (net (code "57") (name "Net-(U$1H-K)") (class "Default")
      (node (ref "R12") (pin "1") (pinfunction "1_1") (pintype "passive"))
      (node (ref "R35") (pin "1") (pinfunction "1_1") (pintype "passive"))
      (node (ref "U$1") (pin "7") (pinfunction "K_7") (pintype "passive"))
    )
    (net (code "58") (name "Net-(U$1I-K)") (class "Default")
      (node (ref "R1") (pin "1") (pinfunction "1_1") (pintype "passive"))
      (node (ref "R34") (pin "1") (pinfunction "1_1") (pintype "passive"))
      (node (ref "U$1") (pin "8") (pinfunction "K_8") (pintype "passive"))
    )
    (net (code "59") (name "Net-(U1-VOUT)") (class "Default")
      (node (ref "C20") (pin "1") (pinfunction "1_1") (pintype "passive"))
      (node (ref "R32") (pin "2") (pinfunction "2_2") (pintype "passive"))
      (node (ref "R33") (pin "2") (pinfunction "2_2") (pintype "passive"))
      (node (ref "R34") (pin "2") (pinfunction "2_2") (pintype "passive"))
      (node (ref "R35") (pin "2") (pinfunction "2_2") (pintype "passive"))
      (node (ref "TR2") (pin "1") (pinfunction "1_1") (pintype "passive"))
      (node (ref "U1") (pin "2") (pinfunction "VOUT_2") (pintype "output"))
    )
    (net (code "60") (name "Net-(X3A-F)") (class "Default")
      (node (ref "R38") (pin "1") (pinfunction "1_1") (pintype "passive"))
      (node (ref "X3") (pin "1") (pinfunction "F_1") (pintype "passive"))
    )
    (net (code "61") (name "Net-(X3C-F)") (class "Default")
      (node (ref "R10") (pin "1") (pinfunction "1_1") (pintype "passive"))
      (node (ref "R8") (pin "1") (pinfunction "1_1") (pintype "passive"))
      (node (ref "X3") (pin "3") (pinfunction "F_3") (pintype "passive"))
    )
    (net (code "62") (name "Net-(X3D-F)") (class "Default")
      (node (ref "R7") (pin "1") (pinfunction "1_1") (pintype "passive"))
      (node (ref "R9") (pin "2") (pinfunction "2_2") (pintype "passive"))
      (node (ref "X3") (pin "4") (pinfunction "F_4") (pintype "passive"))
    )
    (net (code "63") (name "Net-(X3F-F)") (class "Default")
      (node (ref "R23") (pin "1") (pinfunction "1_1") (pintype "passive"))
      (node (ref "X3") (pin "6") (pinfunction "F_6") (pintype "passive"))
    )
    (net (code "64") (name "unconnected-(H1-Pad1)") (class "Default")
      (node (ref "H1") (pin "1") (pinfunction "1_1") (pintype "passive"))
    )
    (net (code "65") (name "unconnected-(H2-Pad1)") (class "Default")
      (node (ref "H2") (pin "1") (pinfunction "1_1") (pintype "passive"))
    )
    (net (code "66") (name "unconnected-(H3-Pad1)") (class "Default")
      (node (ref "H3") (pin "1") (pinfunction "1_1") (pintype "passive"))
    )
    (net (code "67") (name "unconnected-(H4-Pad1)") (class "Default")
      (node (ref "H4") (pin "1") (pinfunction "1_1") (pintype "passive"))
    )
    (net (code "68") (name "unconnected-(H9-Pad1)") (class "Default")
      (node (ref "H9") (pin "1") (pinfunction "1_1") (pintype "passive"))
    )
    (net (code "69") (name "unconnected-(H10-Pad1)") (class "Default")
      (node (ref "H10") (pin "1") (pinfunction "1_1") (pintype "passive"))
    )
    (net (code "70") (name "unconnected-(JP3-Pad6)") (class "Default")
      (node (ref "JP3") (pin "6") (pinfunction "6_6") (pintype "passive"))
    )
    (net (code "71") (name "unconnected-(STM32F03K6T6-NRST-Pad4)") (class "Default")
      (node (ref "STM32F03K6T6") (pin "4") (pinfunction "NRST_4") (pintype "bidirectional"))
    )
    (net (code "72") (name "unconnected-(STM32F03K6T6-PA4-Pad10)") (class "Default")
      (node (ref "STM32F03K6T6") (pin "10") (pinfunction "PA4_10") (pintype "bidirectional"))
    )
    (net (code "73") (name "unconnected-(STM32F03K6T6-PA6-Pad12)") (class "Default")
      (node (ref "STM32F03K6T6") (pin "12") (pinfunction "PA6_12") (pintype "bidirectional"))
    )
    (net (code "74") (name "unconnected-(STM32F03K6T6-PA7-Pad13)") (class "Default")
      (node (ref "STM32F03K6T6") (pin "13") (pinfunction "PA7_13") (pintype "bidirectional"))
    )
    (net (code "75") (name "unconnected-(STM32F03K6T6-PA8-Pad18)") (class "Default")
      (node (ref "STM32F03K6T6") (pin "18") (pinfunction "PA8_18") (pintype "bidirectional"))
    )
    (net (code "76") (name "unconnected-(STM32F03K6T6-PA10-Pad20)") (class "Default")
      (node (ref "STM32F03K6T6") (pin "20") (pinfunction "PA10_20") (pintype "bidirectional"))
    )
    (net (code "77") (name "unconnected-(STM32F03K6T6-PA12-Pad22)") (class "Default")
      (node (ref "STM32F03K6T6") (pin "22") (pinfunction "PA12_22") (pintype "bidirectional"))
    )
    (net (code "78") (name "unconnected-(STM32F03K6T6-PB0-Pad14)") (class "Default")
      (node (ref "STM32F03K6T6") (pin "14") (pinfunction "PB0_14") (pintype "bidirectional"))
    )
    (net (code "79") (name "unconnected-(STM32F03K6T6-PB1-Pad15)") (class "Default")
      (node (ref "STM32F03K6T6") (pin "15") (pinfunction "PB1_15") (pintype "bidirectional"))
    )
    (net (code "80") (name "unconnected-(STM32F03K6T6-PB3-Pad26)") (class "Default")
      (node (ref "STM32F03K6T6") (pin "26") (pinfunction "PB3_26") (pintype "bidirectional"))
    )
  )
)
